# NB_BaseStation.net
KiCad netlist of a schematic drawn in Altium Designer
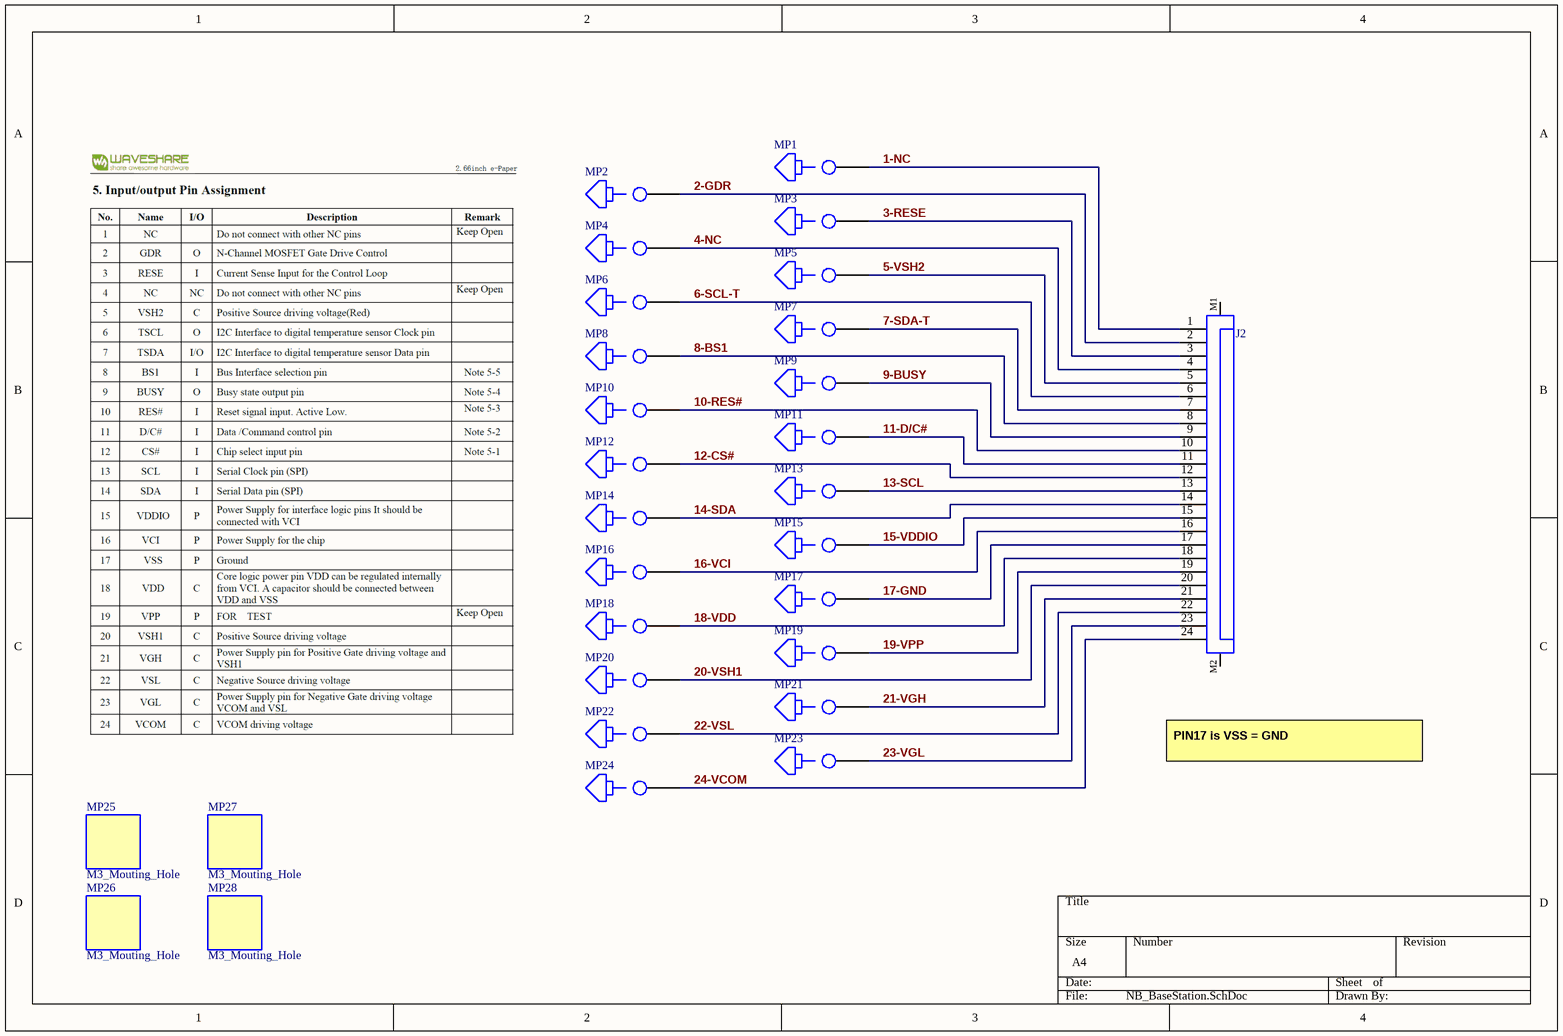
[diagram p0: NB_BaseStation.SchDoc]

(export (version "E")
  (design (tool "Eeschema 10.0.6"))
  (components
    (comp (ref "J2")
      (value "687124182122")
      (footprint "687124182122")
      (description "WR-FPC SMT ZIF Horizontal Dual Contact, pitch 0.5mm, Horizontal, 24pins")
      (fields (field (name "MANUFACTURER") "Wurth Elektronik"))
      (libsource (lib "Schlib") (part "687124182122"))
    )
    (comp (ref "MP1")
      (value "PH-MVS-4355")
      (footprint "PH-MVS-4355")
      (description "Pogo Pin CONTACT SPRING LOADED SLDR CUP")
      (libsource (lib "Schlib") (part "PH-MVS-4355"))
    )
    (comp (ref "MP2")
      (value "PH-MVS-4355")
      (footprint "PH-MVS-4355")
      (description "Pogo Pin CONTACT SPRING LOADED SLDR CUP")
      (libsource (lib "Schlib") (part "PH-MVS-4355"))
    )
    (comp (ref "MP3")
      (value "PH-MVS-4355")
      (footprint "PH-MVS-4355")
      (description "Pogo Pin CONTACT SPRING LOADED SLDR CUP")
      (libsource (lib "Schlib") (part "PH-MVS-4355"))
    )
    (comp (ref "MP4")
      (value "PH-MVS-4355")
      (footprint "PH-MVS-4355")
      (description "Pogo Pin CONTACT SPRING LOADED SLDR CUP")
      (libsource (lib "Schlib") (part "PH-MVS-4355"))
    )
    (comp (ref "MP5")
      (value "PH-MVS-4355")
      (footprint "PH-MVS-4355")
      (description "Pogo Pin CONTACT SPRING LOADED SLDR CUP")
      (libsource (lib "Schlib") (part "PH-MVS-4355"))
    )
    (comp (ref "MP6")
      (value "PH-MVS-4355")
      (footprint "PH-MVS-4355")
      (description "Pogo Pin CONTACT SPRING LOADED SLDR CUP")
      (libsource (lib "Schlib") (part "PH-MVS-4355"))
    )
    (comp (ref "MP7")
      (value "PH-MVS-4355")
      (footprint "PH-MVS-4355")
      (description "Pogo Pin CONTACT SPRING LOADED SLDR CUP")
      (libsource (lib "Schlib") (part "PH-MVS-4355"))
    )
    (comp (ref "MP8")
      (value "PH-MVS-4355")
      (footprint "PH-MVS-4355")
      (description "Pogo Pin CONTACT SPRING LOADED SLDR CUP")
      (libsource (lib "Schlib") (part "PH-MVS-4355"))
    )
    (comp (ref "MP9")
      (value "PH-MVS-4355")
      (footprint "PH-MVS-4355")
      (description "Pogo Pin CONTACT SPRING LOADED SLDR CUP")
      (libsource (lib "Schlib") (part "PH-MVS-4355"))
    )
    (comp (ref "MP10")
      (value "PH-MVS-4355")
      (footprint "PH-MVS-4355")
      (description "Pogo Pin CONTACT SPRING LOADED SLDR CUP")
      (libsource (lib "Schlib") (part "PH-MVS-4355"))
    )
    (comp (ref "MP11")
      (value "PH-MVS-4355")
      (footprint "PH-MVS-4355")
      (description "Pogo Pin CONTACT SPRING LOADED SLDR CUP")
      (libsource (lib "Schlib") (part "PH-MVS-4355"))
    )
    (comp (ref "MP12")
      (value "PH-MVS-4355")
      (footprint "PH-MVS-4355")
      (description "Pogo Pin CONTACT SPRING LOADED SLDR CUP")
      (libsource (lib "Schlib") (part "PH-MVS-4355"))
    )
    (comp (ref "MP13")
      (value "PH-MVS-4355")
      (footprint "PH-MVS-4355")
      (description "Pogo Pin CONTACT SPRING LOADED SLDR CUP")
      (libsource (lib "Schlib") (part "PH-MVS-4355"))
    )
    (comp (ref "MP14")
      (value "PH-MVS-4355")
      (footprint "PH-MVS-4355")
      (description "Pogo Pin CONTACT SPRING LOADED SLDR CUP")
      (libsource (lib "Schlib") (part "PH-MVS-4355"))
    )
    (comp (ref "MP15")
      (value "PH-MVS-4355")
      (footprint "PH-MVS-4355")
      (description "Pogo Pin CONTACT SPRING LOADED SLDR CUP")
      (libsource (lib "Schlib") (part "PH-MVS-4355"))
    )
    (comp (ref "MP16")
      (value "PH-MVS-4355")
      (footprint "PH-MVS-4355")
      (description "Pogo Pin CONTACT SPRING LOADED SLDR CUP")
      (libsource (lib "Schlib") (part "PH-MVS-4355"))
    )
    (comp (ref "MP17")
      (value "PH-MVS-4355")
      (footprint "PH-MVS-4355")
      (description "Pogo Pin CONTACT SPRING LOADED SLDR CUP")
      (libsource (lib "Schlib") (part "PH-MVS-4355"))
    )
    (comp (ref "MP18")
      (value "PH-MVS-4355")
      (footprint "PH-MVS-4355")
      (description "Pogo Pin CONTACT SPRING LOADED SLDR CUP")
      (libsource (lib "Schlib") (part "PH-MVS-4355"))
    )
    (comp (ref "MP19")
      (value "PH-MVS-4355")
      (footprint "PH-MVS-4355")
      (description "Pogo Pin CONTACT SPRING LOADED SLDR CUP")
      (libsource (lib "Schlib") (part "PH-MVS-4355"))
    )
    (comp (ref "MP20")
      (value "PH-MVS-4355")
      (footprint "PH-MVS-4355")
      (description "Pogo Pin CONTACT SPRING LOADED SLDR CUP")
      (libsource (lib "Schlib") (part "PH-MVS-4355"))
    )
    (comp (ref "MP21")
      (value "PH-MVS-4355")
      (footprint "PH-MVS-4355")
      (description "Pogo Pin CONTACT SPRING LOADED SLDR CUP")
      (libsource (lib "Schlib") (part "PH-MVS-4355"))
    )
    (comp (ref "MP22")
      (value "PH-MVS-4355")
      (footprint "PH-MVS-4355")
      (description "Pogo Pin CONTACT SPRING LOADED SLDR CUP")
      (libsource (lib "Schlib") (part "PH-MVS-4355"))
    )
    (comp (ref "MP23")
      (value "PH-MVS-4355")
      (footprint "PH-MVS-4355")
      (description "Pogo Pin CONTACT SPRING LOADED SLDR CUP")
      (libsource (lib "Schlib") (part "PH-MVS-4355"))
    )
    (comp (ref "MP24")
      (value "PH-MVS-4355")
      (footprint "PH-MVS-4355")
      (description "Pogo Pin CONTACT SPRING LOADED SLDR CUP")
      (libsource (lib "Schlib") (part "PH-MVS-4355"))
    )
    (comp (ref "MP25")
      (value "M3_Mouting_Hole")
      (footprint "M3_Mouting_Hole")
      (libsource (lib "Schlib") (part "M3_Mouting_Hole"))
    )
    (comp (ref "MP26")
      (value "M3_Mouting_Hole")
      (footprint "M3_Mouting_Hole")
      (libsource (lib "Schlib") (part "M3_Mouting_Hole"))
    )
    (comp (ref "MP27")
      (value "M3_Mouting_Hole")
      (footprint "M3_Mouting_Hole")
      (libsource (lib "Schlib") (part "M3_Mouting_Hole"))
    )
    (comp (ref "MP28")
      (value "M3_Mouting_Hole")
      (footprint "M3_Mouting_Hole")
      (libsource (lib "Schlib") (part "M3_Mouting_Hole"))
    )
  )
  (nets
    (net (code "1") (name "/1-NC") (class "Default")
      (node (ref "J2") (pin "1") (pinfunction "1_1") (pintype "passive"))
      (node (ref "MP1") (pin "1") (pintype "passive"))
    )
    (net (code "2") (name "/2-GDR") (class "Default")
      (node (ref "J2") (pin "2") (pinfunction "2_2") (pintype "passive"))
      (node (ref "MP2") (pin "1") (pintype "passive"))
    )
    (net (code "3") (name "/3-RESE") (class "Default")
      (node (ref "J2") (pin "3") (pinfunction "3_3") (pintype "passive"))
      (node (ref "MP3") (pin "1") (pintype "passive"))
    )
    (net (code "4") (name "/4-NC") (class "Default")
      (node (ref "J2") (pin "4") (pinfunction "4_4") (pintype "passive"))
      (node (ref "MP4") (pin "1") (pintype "passive"))
    )
    (net (code "5") (name "/5-VSH2") (class "Default")
      (node (ref "J2") (pin "5") (pinfunction "5_5") (pintype "passive"))
      (node (ref "MP5") (pin "1") (pintype "passive"))
    )
    (net (code "6") (name "/6-SCL-T") (class "Default")
      (node (ref "J2") (pin "6") (pinfunction "6_6") (pintype "passive"))
      (node (ref "MP6") (pin "1") (pintype "passive"))
    )
    (net (code "7") (name "/7-SDA-T") (class "Default")
      (node (ref "J2") (pin "7") (pinfunction "7_7") (pintype "passive"))
      (node (ref "MP7") (pin "1") (pintype "passive"))
    )
    (net (code "8") (name "/8-BS1") (class "Default")
      (node (ref "J2") (pin "8") (pinfunction "8_8") (pintype "passive"))
      (node (ref "MP8") (pin "1") (pintype "passive"))
    )
    (net (code "9") (name "/9-BUSY") (class "Default")
      (node (ref "J2") (pin "9") (pinfunction "9_9") (pintype "passive"))
      (node (ref "MP9") (pin "1") (pintype "passive"))
    )
    (net (code "10") (name "/10-RES#") (class "Default")
      (node (ref "J2") (pin "10") (pinfunction "10_10") (pintype "passive"))
      (node (ref "MP10") (pin "1") (pintype "passive"))
    )
    (net (code "11") (name "/11-D{slash}C#") (class "Default")
      (node (ref "J2") (pin "11") (pinfunction "11_11") (pintype "passive"))
      (node (ref "MP11") (pin "1") (pintype "passive"))
    )
    (net (code "12") (name "/12-CS#") (class "Default")
      (node (ref "J2") (pin "12") (pinfunction "12_12") (pintype "passive"))
      (node (ref "MP12") (pin "1") (pintype "passive"))
    )
    (net (code "13") (name "/13-SCL") (class "Default")
      (node (ref "J2") (pin "13") (pinfunction "13_13") (pintype "passive"))
      (node (ref "MP13") (pin "1") (pintype "passive"))
    )
    (net (code "14") (name "/14-SDA") (class "Default")
      (node (ref "J2") (pin "14") (pinfunction "14_14") (pintype "passive"))
      (node (ref "MP14") (pin "1") (pintype "passive"))
    )
    (net (code "15") (name "/15-VDDIO") (class "Default")
      (node (ref "J2") (pin "15") (pinfunction "15_15") (pintype "passive"))
      (node (ref "MP15") (pin "1") (pintype "passive"))
    )
    (net (code "16") (name "/16-VCI") (class "Default")
      (node (ref "J2") (pin "16") (pinfunction "16_16") (pintype "passive"))
      (node (ref "MP16") (pin "1") (pintype "passive"))
    )
    (net (code "17") (name "/17-GND") (class "Default")
      (node (ref "J2") (pin "17") (pinfunction "17_17") (pintype "passive"))
      (node (ref "MP17") (pin "1") (pintype "passive"))
    )
    (net (code "18") (name "/18-VDD") (class "Default")
      (node (ref "J2") (pin "18") (pinfunction "18_18") (pintype "passive"))
      (node (ref "MP18") (pin "1") (pintype "passive"))
    )
    (net (code "19") (name "/19-VPP") (class "Default")
      (node (ref "J2") (pin "19") (pinfunction "19_19") (pintype "passive"))
      (node (ref "MP19") (pin "1") (pintype "passive"))
    )
    (net (code "20") (name "/20-VSH1") (class "Default")
      (node (ref "J2") (pin "20") (pinfunction "20_20") (pintype "passive"))
      (node (ref "MP20") (pin "1") (pintype "passive"))
    )
    (net (code "21") (name "/21-VGH") (class "Default")
      (node (ref "J2") (pin "21") (pinfunction "21_21") (pintype "passive"))
      (node (ref "MP21") (pin "1") (pintype "passive"))
    )
    (net (code "22") (name "/22-VSL") (class "Default")
      (node (ref "J2") (pin "22") (pinfunction "22_22") (pintype "passive"))
      (node (ref "MP22") (pin "1") (pintype "passive"))
    )
    (net (code "23") (name "/23-VGL") (class "Default")
      (node (ref "J2") (pin "23") (pinfunction "23_23") (pintype "passive"))
      (node (ref "MP23") (pin "1") (pintype "passive"))
    )
    (net (code "24") (name "/24-VCOM") (class "Default")
      (node (ref "J2") (pin "24") (pinfunction "24_24") (pintype "passive"))
      (node (ref "MP24") (pin "1") (pintype "passive"))
    )
    (net (code "25") (name "unconnected-(J2-PadM1)") (class "Default")
      (node (ref "J2") (pin "M1") (pinfunction "M1_M1") (pintype "passive"))
    )
    (net (code "26") (name "unconnected-(J2-PadM2)") (class "Default")
      (node (ref "J2") (pin "M2") (pinfunction "M2_M2") (pintype "passive"))
    )
  )
)
